# MINI_SAM_D51_r017_b002_A.net
KiCad netlist of a schematic drawn in EAGLE
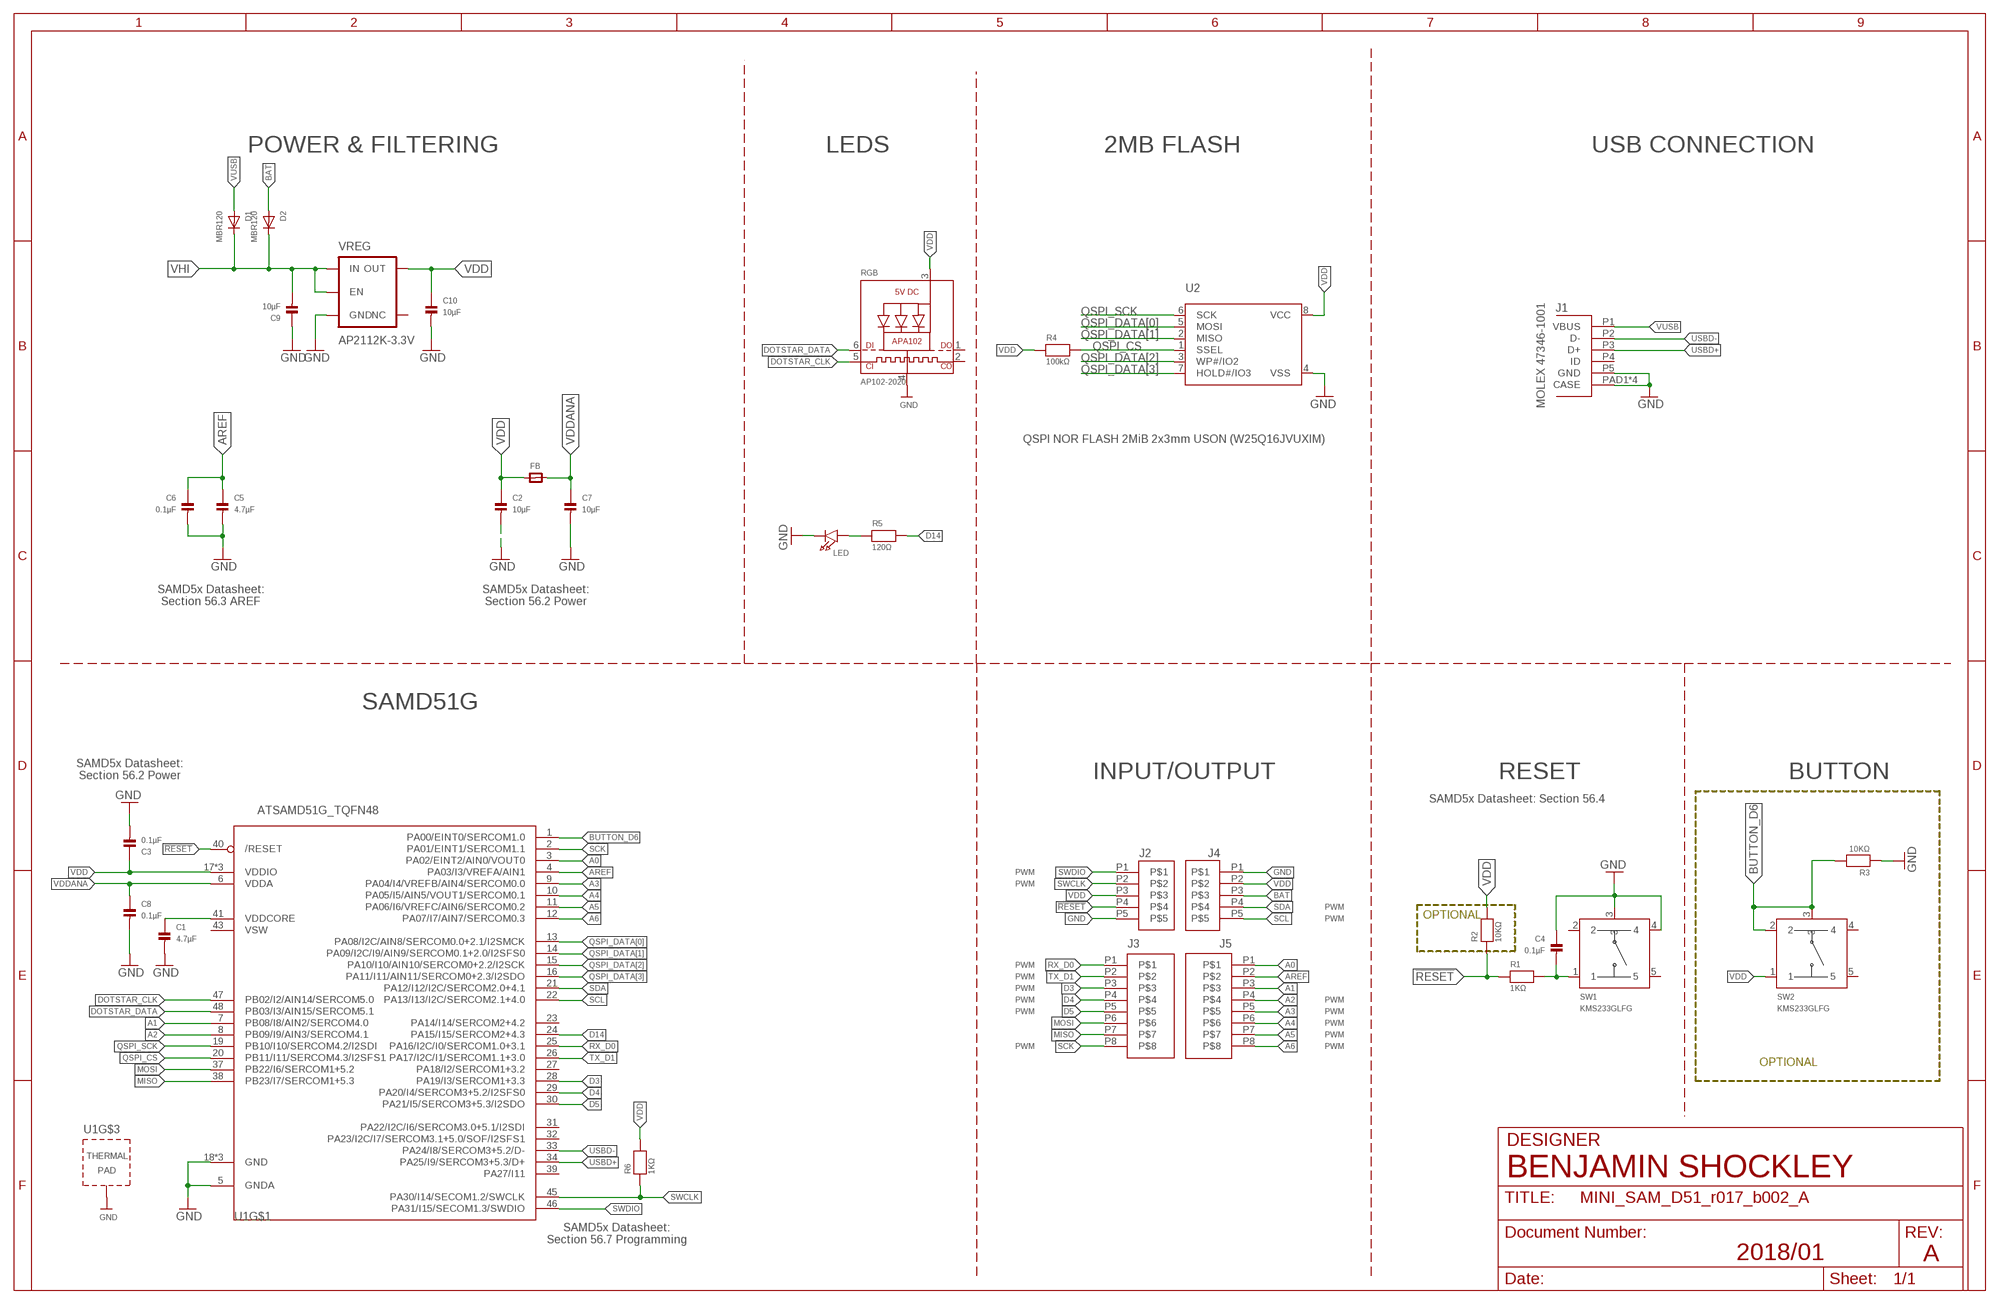
[diagram p0: schematic, sheet 1]

(export (version "E")
  (design (tool "Eeschema 10.0.6"))
  (components
    (comp (ref "C1")
      (value "4.7µF")
      (footprint "eagle-import:_0603MP")
      (libsource (lib "eagle-import") (part "CAP_CERAMIC_0603MP"))
    )
    (comp (ref "C2")
      (value "10µF")
      (footprint "eagle-import:_0603MP")
      (libsource (lib "eagle-import") (part "CAP_CERAMIC_0603MP"))
    )
    (comp (ref "C3")
      (value "0.1µF")
      (footprint "eagle-import:_0603MP")
      (libsource (lib "eagle-import") (part "CAP_CERAMIC_0603MP"))
    )
    (comp (ref "C4")
      (value "0.1µF")
      (footprint "eagle-import:_0603MP")
      (libsource (lib "eagle-import") (part "CAP_CERAMIC_0603MP"))
    )
    (comp (ref "C5")
      (value "4.7µF")
      (footprint "eagle-import:_0603MP")
      (libsource (lib "eagle-import") (part "CAP_CERAMIC_0603MP"))
    )
    (comp (ref "C6")
      (value "0.1µF")
      (footprint "eagle-import:_0603MP")
      (libsource (lib "eagle-import") (part "CAP_CERAMIC_0603MP"))
    )
    (comp (ref "C7")
      (value "10µF")
      (footprint "eagle-import:_0603MP")
      (libsource (lib "eagle-import") (part "CAP_CERAMIC_0603MP"))
    )
    (comp (ref "C8")
      (value "0.1µF")
      (footprint "eagle-import:_0603MP")
      (libsource (lib "eagle-import") (part "CAP_CERAMIC_0603MP"))
    )
    (comp (ref "C9")
      (value "10µF")
      (footprint "eagle-import:_0603MP")
      (libsource (lib "eagle-import") (part "CAP_CERAMIC_0603MP"))
    )
    (comp (ref "C10")
      (value "10µF")
      (footprint "eagle-import:_0603MP")
      (libsource (lib "eagle-import") (part "CAP_CERAMIC_0603MP"))
    )
    (comp (ref "D1")
      (value "MBR120")
      (footprint "eagle-import:SOD-123FL")
      (libsource (lib "eagle-import") (part "DIODE_SOD-123FL"))
    )
    (comp (ref "D2")
      (value "MBR120")
      (footprint "eagle-import:SOD-123FL")
      (libsource (lib "eagle-import") (part "DIODE_SOD-123FL"))
    )
    (comp (ref "FB")
      (value "Impedence: 50 ohm @ 20 MHz, 220 Ohm @ 100 MHz; low DC resistance")
      (footprint "eagle-import:_0603MP")
      (libsource (lib "eagle-import") (part "FERRITE_0603MP"))
    )
    (comp (ref "J1")
      (value "MOLEX_47346-100147346")
      (footprint "eagle-import:MOLEX_47346-1001")
      (libsource (lib "eagle-import") (part "MOLEX_47346-100147346"))
    )
    (comp (ref "J2")
      (value "1X5_HEADER_1.27MMCAST")
      (footprint "eagle-import:1X5_HEADER_1.27MM_CASTELLATED")
      (libsource (lib "eagle-import") (part "1X5_HEADER_1.27MMCAST"))
    )
    (comp (ref "J3")
      (value "1X8_HEADER_1.27MMCAST")
      (footprint "eagle-import:1X8_HEADER_1.27MM_CASTELLATED")
      (libsource (lib "eagle-import") (part "1X8_HEADER_1.27MMCAST"))
    )
    (comp (ref "J4")
      (value "1X5_HEADER_1.27MMCAST")
      (footprint "eagle-import:1X5_HEADER_1.27MM_CASTELLATED")
      (libsource (lib "eagle-import") (part "1X5_HEADER_1.27MMCAST"))
    )
    (comp (ref "J5")
      (value "1X8_HEADER_1.27MMCAST")
      (footprint "eagle-import:1X8_HEADER_1.27MM_CASTELLATED")
      (libsource (lib "eagle-import") (part "1X8_HEADER_1.27MMCAST"))
    )
    (comp (ref "LED")
      (value "VLRK31Q1R2-GS08")
      (footprint "eagle-import:REVERSE_MOUNT_LED")
      (libsource (lib "eagle-import") (part "REVERSEMOUNTLED"))
    )
    (comp (ref "R1")
      (value "1KΩ")
      (footprint "eagle-import:_0603MP")
      (libsource (lib "eagle-import") (part "RESISTOR_0603MP"))
    )
    (comp (ref "R2")
      (value "10KΩ")
      (footprint "eagle-import:_0603MP")
      (libsource (lib "eagle-import") (part "RESISTOR_0603MP"))
    )
    (comp (ref "R3")
      (value "10KΩ")
      (footprint "eagle-import:_0603MP")
      (libsource (lib "eagle-import") (part "RESISTOR_0603MP"))
    )
    (comp (ref "R4")
      (value "100kΩ")
      (footprint "eagle-import:_0603MP")
      (libsource (lib "eagle-import") (part "RESISTOR_0603MP"))
    )
    (comp (ref "R5")
      (value "120Ω")
      (footprint "eagle-import:_0603MP")
      (libsource (lib "eagle-import") (part "RESISTOR_0603MP"))
    )
    (comp (ref "R6")
      (value "1KΩ")
      (footprint "eagle-import:_0603MP")
      (libsource (lib "eagle-import") (part "RESISTOR_0603MP"))
    )
    (comp (ref "RGB")
      (value "AP102-2020")
      (footprint "eagle-import:APA102_2020")
      (libsource (lib "eagle-import") (part "APA1022020"))
    )
    (comp (ref "SW1")
      (value "KMS233GLFG")
      (footprint "eagle-import:KMS_SWITCH")
      (libsource (lib "eagle-import") (part "KMS_SWITCHKMS"))
    )
    (comp (ref "SW2")
      (value "KMS233GLFG")
      (footprint "eagle-import:KMS_SWITCH")
      (libsource (lib "eagle-import") (part "KMS_SWITCHKMS"))
    )
    (comp (ref "U1")
      (value "ATSAMD51G_TQFN48")
      (footprint "eagle-import:TQFN48_7MM")
      (libsource (lib "eagle-import") (part "ATSAMD51G_TQFN48"))
    )
    (comp (ref "U2")
      (value "QSPI NOR FLASH 2MiB 2x3mm USON (W25Q16JVUXIM)")
      (footprint "eagle-import:USON8")
      (libsource (lib "eagle-import") (part "SPIFLASH_8PINUX"))
    )
    (comp (ref "VREG")
      (value "AP2112K-3.3V")
      (footprint "eagle-import:SOT23-5")
      (libsource (lib "eagle-import") (part "V_REG_AP2112K-3.3V"))
    )
  )
  (nets
    (net (code "1") (name "/VSW") (class "Default")
      (node (ref "U1") (pin "43") (pinfunction "VSW_43") (pintype "power_in"))
    )
    (net (code "2") (name "/~{RESET}") (class "Default")
      (node (ref "J2") (pin "P4") (pinfunction "P$4_P4") (pintype "bidirectional"))
      (node (ref "R1") (pin "1") (pinfunction "1_1") (pintype "passive"))
      (node (ref "R2") (pin "1") (pinfunction "1_1") (pintype "passive"))
      (node (ref "U1") (pin "40") (pinfunction "/RESET_40") (pintype "bidirectional"))
    )
    (net (code "3") (name "A0") (class "Default")
      (node (ref "J5") (pin "P1") (pinfunction "P$1_P1") (pintype "bidirectional"))
      (node (ref "U1") (pin "3") (pinfunction "PA02/EINT2/AIN0/VOUT0_3") (pintype "bidirectional"))
    )
    (net (code "4") (name "A1") (class "Default")
      (node (ref "J5") (pin "P3") (pinfunction "P$3_P3") (pintype "bidirectional"))
      (node (ref "U1") (pin "7") (pinfunction "PB08/I8/AIN2/SERCOM4.0_7") (pintype "bidirectional"))
    )
    (net (code "5") (name "A2") (class "Default")
      (node (ref "J5") (pin "P4") (pinfunction "P$4_P4") (pintype "bidirectional"))
      (node (ref "U1") (pin "8") (pinfunction "PB09/I9/AIN3/SERCOM4.1_8") (pintype "bidirectional"))
    )
    (net (code "6") (name "A3") (class "Default")
      (node (ref "J5") (pin "P5") (pinfunction "P$5_P5") (pintype "bidirectional"))
      (node (ref "U1") (pin "9") (pinfunction "PA04/I4/VREFB/AIN4/SERCOM0.0_9") (pintype "bidirectional"))
    )
    (net (code "7") (name "A4") (class "Default")
      (node (ref "J5") (pin "P6") (pinfunction "P$6_P6") (pintype "bidirectional"))
      (node (ref "U1") (pin "10") (pinfunction "PA05/I5/AIN5/VOUT1/SERCOM0.1_10") (pintype "bidirectional"))
    )
    (net (code "8") (name "A5") (class "Default")
      (node (ref "J5") (pin "P7") (pinfunction "P$7_P7") (pintype "bidirectional"))
      (node (ref "U1") (pin "11") (pinfunction "PA06/I6/VREFC/AIN6/SERCOM0.2_11") (pintype "bidirectional"))
    )
    (net (code "9") (name "A6") (class "Default")
      (node (ref "J5") (pin "P8") (pinfunction "P$8_P8") (pintype "bidirectional"))
      (node (ref "U1") (pin "12") (pinfunction "PA07/I7/AIN7/SERCOM0.3_12") (pintype "bidirectional"))
    )
    (net (code "10") (name "AREF") (class "Default")
      (node (ref "C5") (pin "1") (pinfunction "P$1_1") (pintype "passive"))
      (node (ref "C6") (pin "1") (pinfunction "P$1_1") (pintype "passive"))
      (node (ref "J5") (pin "P2") (pinfunction "P$2_P2") (pintype "bidirectional"))
      (node (ref "U1") (pin "4") (pinfunction "PA03/I3/VREFA/AIN1_4") (pintype "bidirectional"))
    )
    (net (code "11") (name "BAT") (class "Default")
      (node (ref "D2") (pin "A") (pinfunction "A_A") (pintype "passive"))
      (node (ref "J4") (pin "P3") (pinfunction "P$3_P3") (pintype "bidirectional"))
    )
    (net (code "12") (name "BUTTON_D6") (class "Default")
      (node (ref "R3") (pin "2") (pinfunction "2_2") (pintype "passive"))
      (node (ref "SW2") (pin "2") (pinfunction "2_2") (pintype "bidirectional"))
      (node (ref "SW2") (pin "3") (pinfunction "3_3") (pintype "bidirectional"))
      (node (ref "U1") (pin "1") (pinfunction "PA00/EINT0/SERCOM1.0_1") (pintype "bidirectional"))
    )
    (net (code "13") (name "D3") (class "Default")
      (node (ref "J3") (pin "P3") (pinfunction "P$3_P3") (pintype "bidirectional"))
      (node (ref "U1") (pin "28") (pinfunction "PA19/I3/SERCOM1+3.3_28") (pintype "bidirectional"))
    )
    (net (code "14") (name "D4") (class "Default")
      (node (ref "J3") (pin "P4") (pinfunction "P$4_P4") (pintype "bidirectional"))
      (node (ref "U1") (pin "29") (pinfunction "PA20/I4/SERCOM3+5.2/I2SFS0_29") (pintype "bidirectional"))
    )
    (net (code "15") (name "D5") (class "Default")
      (node (ref "J3") (pin "P5") (pinfunction "P$5_P5") (pintype "bidirectional"))
      (node (ref "U1") (pin "30") (pinfunction "PA21/I5/SERCOM3+5.3/I2SDO_30") (pintype "bidirectional"))
    )
    (net (code "16") (name "D14") (class "Default")
      (node (ref "R5") (pin "2") (pinfunction "2_2") (pintype "passive"))
      (node (ref "U1") (pin "24") (pinfunction "PA15/I15/SERCOM2+4.3_24") (pintype "bidirectional"))
    )
    (net (code "17") (name "DOTSTAR_CLK") (class "Default")
      (node (ref "RGB") (pin "5") (pinfunction "CKI_5") (pintype "input"))
      (node (ref "U1") (pin "47") (pinfunction "PB02/I2/AIN14/SERCOM5.0_47") (pintype "bidirectional"))
    )
    (net (code "18") (name "DOTSTAR_DATA") (class "Default")
      (node (ref "RGB") (pin "6") (pinfunction "DI_6") (pintype "input"))
      (node (ref "U1") (pin "48") (pinfunction "PB03/I3/AIN15/SERCOM5.1_48") (pintype "bidirectional"))
    )
    (net (code "19") (name "GND") (class "Default")
      (node (ref "C1") (pin "2") (pinfunction "P$2_2") (pintype "passive"))
      (node (ref "C10") (pin "2") (pinfunction "P$2_2") (pintype "passive"))
      (node (ref "C2") (pin "2") (pinfunction "P$2_2") (pintype "passive"))
      (node (ref "C3") (pin "2") (pinfunction "P$2_2") (pintype "passive"))
      (node (ref "C4") (pin "1") (pinfunction "P$1_1") (pintype "passive"))
      (node (ref "C5") (pin "2") (pinfunction "P$2_2") (pintype "passive"))
      (node (ref "C6") (pin "2") (pinfunction "P$2_2") (pintype "passive"))
      (node (ref "C7") (pin "2") (pinfunction "P$2_2") (pintype "passive"))
      (node (ref "C8") (pin "2") (pinfunction "P$2_2") (pintype "passive"))
      (node (ref "C9") (pin "1") (pinfunction "P$1_1") (pintype "passive"))
      (node (ref "J1") (pin "P5") (pinfunction "GND_P5") (pintype "power_in"))
      (node (ref "J1") (pin "PAD1") (pinfunction "CASE_PAD1") (pintype "bidirectional"))
      (node (ref "J1") (pin "PAD2") (pinfunction "CASE_PAD2") (pintype "bidirectional"))
      (node (ref "J1") (pin "PAD3") (pinfunction "CASE_PAD3") (pintype "bidirectional"))
      (node (ref "J1") (pin "PAD4") (pinfunction "CASE_PAD4") (pintype "bidirectional"))
      (node (ref "J2") (pin "P5") (pinfunction "P$5_P5") (pintype "bidirectional"))
      (node (ref "J4") (pin "P1") (pinfunction "P$1_P1") (pintype "bidirectional"))
      (node (ref "LED") (pin "C") (pinfunction "C_C") (pintype "passive"))
      (node (ref "R3") (pin "1") (pinfunction "1_1") (pintype "passive"))
      (node (ref "RGB") (pin "4") (pinfunction "GND_4") (pintype "power_in"))
      (node (ref "SW1") (pin "3") (pinfunction "3_3") (pintype "bidirectional"))
      (node (ref "SW1") (pin "4") (pinfunction "4_4") (pintype "bidirectional"))
      (node (ref "U1") (pin "18") (pinfunction "GND_18") (pintype "power_in"))
      (node (ref "U1") (pin "35") (pinfunction "GND_35") (pintype "power_in"))
      (node (ref "U1") (pin "42") (pinfunction "GND_42") (pintype "power_in"))
      (node (ref "U1") (pin "5") (pinfunction "GNDA_5") (pintype "power_in"))
      (node (ref "U1") (pin "THERMAL") (pinfunction "TP_THERMAL") (pintype "power_in"))
      (node (ref "U2") (pin "4") (pinfunction "VSS_4") (pintype "bidirectional"))
      (node (ref "VREG") (pin "2") (pinfunction "GND_2") (pintype "input"))
    )
    (net (code "20") (name "MISO") (class "Default")
      (node (ref "J3") (pin "P7") (pinfunction "P$7_P7") (pintype "bidirectional"))
      (node (ref "U1") (pin "38") (pinfunction "PB23/I7/SERCOM1+5.3_38") (pintype "bidirectional"))
    )
    (net (code "21") (name "MOSI") (class "Default")
      (node (ref "J3") (pin "P6") (pinfunction "P$6_P6") (pintype "bidirectional"))
      (node (ref "U1") (pin "37") (pinfunction "PB22/I6/SERCOM1+5.2_37") (pintype "bidirectional"))
    )
    (net (code "22") (name "Net-(C1-P$1)") (class "Default")
      (node (ref "C1") (pin "1") (pinfunction "P$1_1") (pintype "passive"))
      (node (ref "U1") (pin "41") (pinfunction "VDDCORE_41") (pintype "power_in"))
    )
    (net (code "23") (name "Net-(C4-P$2)") (class "Default")
      (node (ref "C4") (pin "2") (pinfunction "P$2_2") (pintype "passive"))
      (node (ref "R1") (pin "2") (pinfunction "2_2") (pintype "passive"))
      (node (ref "SW1") (pin "1") (pinfunction "1_1") (pintype "bidirectional"))
    )
    (net (code "24") (name "Net-(LED-PadA)") (class "Default")
      (node (ref "LED") (pin "A") (pinfunction "A_A") (pintype "passive"))
      (node (ref "R5") (pin "1") (pinfunction "1_1") (pintype "passive"))
    )
    (net (code "25") (name "QSPI_CS") (class "Default")
      (node (ref "R4") (pin "2") (pinfunction "2_2") (pintype "passive"))
      (node (ref "U1") (pin "20") (pinfunction "PB11/I11/SERCOM4.3/I2SFS1_20") (pintype "bidirectional"))
      (node (ref "U2") (pin "1") (pinfunction "SSEL_1") (pintype "bidirectional"))
    )
    (net (code "26") (name "QSPI_DATA[0]") (class "Default")
      (node (ref "U1") (pin "13") (pinfunction "PA08/I2C/AIN8/SERCOM0.0+2.1/I2SMCK_13") (pintype "bidirectional"))
      (node (ref "U2") (pin "5") (pinfunction "MOSI_5") (pintype "bidirectional"))
    )
    (net (code "27") (name "QSPI_DATA[1]") (class "Default")
      (node (ref "U1") (pin "14") (pinfunction "PA09/I2C/I9/AIN9/SERCOM0.1+2.0/I2SFS0_14") (pintype "bidirectional"))
      (node (ref "U2") (pin "2") (pinfunction "MISO_2") (pintype "bidirectional"))
    )
    (net (code "28") (name "QSPI_DATA[2]") (class "Default")
      (node (ref "U1") (pin "15") (pinfunction "PA10/I10/AIN10/SERCOM0+2.2/I2SCK_15") (pintype "bidirectional"))
      (node (ref "U2") (pin "3") (pinfunction "WP#/IO2_3") (pintype "bidirectional"))
    )
    (net (code "29") (name "QSPI_DATA[3]") (class "Default")
      (node (ref "U1") (pin "16") (pinfunction "PA11/I11/AIN11/SERCOM0+2.3/I2SDO_16") (pintype "bidirectional"))
      (node (ref "U2") (pin "7") (pinfunction "HOLD#/IO3_7") (pintype "bidirectional"))
    )
    (net (code "30") (name "QSPI_SCK") (class "Default")
      (node (ref "U1") (pin "19") (pinfunction "PB10/I10/SERCOM4.2/I2SDI_19") (pintype "bidirectional"))
      (node (ref "U2") (pin "6") (pinfunction "SCK_6") (pintype "bidirectional"))
    )
    (net (code "31") (name "RX_D0") (class "Default")
      (node (ref "J3") (pin "P1") (pinfunction "P$1_P1") (pintype "bidirectional"))
      (node (ref "U1") (pin "25") (pinfunction "PA16/I2C/I0/SERCOM1.0+3.1_25") (pintype "bidirectional"))
    )
    (net (code "32") (name "SCK") (class "Default")
      (node (ref "J3") (pin "P8") (pinfunction "P$8_P8") (pintype "bidirectional"))
      (node (ref "U1") (pin "2") (pinfunction "PA01/EINT1/SERCOM1.1_2") (pintype "bidirectional"))
    )
    (net (code "33") (name "SCL") (class "Default")
      (node (ref "J4") (pin "P5") (pinfunction "P$5_P5") (pintype "bidirectional"))
      (node (ref "U1") (pin "22") (pinfunction "PA13/I13/I2C/SERCOM2.1+4.0_22") (pintype "bidirectional"))
    )
    (net (code "34") (name "SDA") (class "Default")
      (node (ref "J4") (pin "P4") (pinfunction "P$4_P4") (pintype "bidirectional"))
      (node (ref "U1") (pin "21") (pinfunction "PA12/I12/I2C/SERCOM2.0+4.1_21") (pintype "bidirectional"))
    )
    (net (code "35") (name "SWCLK") (class "Default")
      (node (ref "J2") (pin "P2") (pinfunction "P$2_P2") (pintype "bidirectional"))
      (node (ref "R6") (pin "1") (pinfunction "1_1") (pintype "passive"))
      (node (ref "U1") (pin "45") (pinfunction "PA30/I14/SECOM1.2/SWCLK_45") (pintype "bidirectional"))
    )
    (net (code "36") (name "SWDIO") (class "Default")
      (node (ref "J2") (pin "P1") (pinfunction "P$1_P1") (pintype "bidirectional"))
      (node (ref "U1") (pin "46") (pinfunction "PA31/I15/SECOM1.3/SWDIO_46") (pintype "bidirectional"))
    )
    (net (code "37") (name "TX_D1") (class "Default")
      (node (ref "J3") (pin "P2") (pinfunction "P$2_P2") (pintype "bidirectional"))
      (node (ref "U1") (pin "26") (pinfunction "PA17/I2C/I1/SERCOM1.1+3.0_26") (pintype "bidirectional"))
    )
    (net (code "38") (name "USBD+") (class "Default")
      (node (ref "J1") (pin "P3") (pinfunction "D+_P3") (pintype "bidirectional"))
      (node (ref "U1") (pin "34") (pinfunction "PA25/I9/SERCOM3+5.3/D+_34") (pintype "bidirectional"))
    )
    (net (code "39") (name "USBD-") (class "Default")
      (node (ref "J1") (pin "P2") (pinfunction "D-_P2") (pintype "bidirectional"))
      (node (ref "U1") (pin "33") (pinfunction "PA24/I8/SERCOM3+5.2/D-_33") (pintype "bidirectional"))
    )
    (net (code "40") (name "VDD") (class "Default")
      (node (ref "C10") (pin "1") (pinfunction "P$1_1") (pintype "passive"))
      (node (ref "C2") (pin "1") (pinfunction "P$1_1") (pintype "passive"))
      (node (ref "C3") (pin "1") (pinfunction "P$1_1") (pintype "passive"))
      (node (ref "FB") (pin "1") (pinfunction "P$1_1") (pintype "passive"))
      (node (ref "J2") (pin "P3") (pinfunction "P$3_P3") (pintype "bidirectional"))
      (node (ref "J4") (pin "P2") (pinfunction "P$2_P2") (pintype "bidirectional"))
      (node (ref "R2") (pin "2") (pinfunction "2_2") (pintype "passive"))
      (node (ref "R4") (pin "1") (pinfunction "1_1") (pintype "passive"))
      (node (ref "R6") (pin "2") (pinfunction "2_2") (pintype "passive"))
      (node (ref "RGB") (pin "3") (pinfunction "VDD_3") (pintype "power_in"))
      (node (ref "SW2") (pin "1") (pinfunction "1_1") (pintype "bidirectional"))
      (node (ref "U1") (pin "17") (pinfunction "VDDIO_17") (pintype "power_in"))
      (node (ref "U1") (pin "36") (pinfunction "VDDIO_36") (pintype "power_in"))
      (node (ref "U1") (pin "44") (pinfunction "VDDIO_44") (pintype "power_in"))
      (node (ref "U2") (pin "8") (pinfunction "VCC_8") (pintype "bidirectional"))
      (node (ref "VREG") (pin "5") (pinfunction "OUT_5") (pintype "passive"))
    )
    (net (code "41") (name "VDDANA") (class "Default")
      (node (ref "C7") (pin "1") (pinfunction "P$1_1") (pintype "passive"))
      (node (ref "C8") (pin "1") (pinfunction "P$1_1") (pintype "passive"))
      (node (ref "FB") (pin "2") (pinfunction "P$2_2") (pintype "passive"))
      (node (ref "U1") (pin "6") (pinfunction "VDDA_6") (pintype "power_in"))
    )
    (net (code "42") (name "VHI") (class "Default")
      (node (ref "C9") (pin "2") (pinfunction "P$2_2") (pintype "passive"))
      (node (ref "D1") (pin "C") (pinfunction "C_C") (pintype "passive"))
      (node (ref "D2") (pin "C") (pinfunction "C_C") (pintype "passive"))
      (node (ref "VREG") (pin "1") (pinfunction "IN_1") (pintype "input"))
      (node (ref "VREG") (pin "3") (pinfunction "EN_3") (pintype "input"))
    )
    (net (code "43") (name "VUSB") (class "Default")
      (node (ref "D1") (pin "A") (pinfunction "A_A") (pintype "passive"))
      (node (ref "J1") (pin "P1") (pinfunction "VBUS_P1") (pintype "power_in"))
    )
    (net (code "44") (name "unconnected-(J1-ID-PadP4)") (class "Default")
      (node (ref "J1") (pin "P4") (pinfunction "ID_P4") (pintype "bidirectional"))
    )
    (net (code "45") (name "unconnected-(RGB-CKO-Pad2)") (class "Default")
      (node (ref "RGB") (pin "2") (pinfunction "CKO_2") (pintype "output"))
    )
    (net (code "46") (name "unconnected-(RGB-DO-Pad1)") (class "Default")
      (node (ref "RGB") (pin "1") (pinfunction "DO_1") (pintype "output"))
    )
    (net (code "47") (name "unconnected-(SW1-Pad2)") (class "Default")
      (node (ref "SW1") (pin "2") (pinfunction "2_2") (pintype "bidirectional"))
    )
    (net (code "48") (name "unconnected-(SW1-Pad5)") (class "Default")
      (node (ref "SW1") (pin "5") (pinfunction "5_5") (pintype "bidirectional"))
    )
    (net (code "49") (name "unconnected-(SW2-Pad4)") (class "Default")
      (node (ref "SW2") (pin "4") (pinfunction "4_4") (pintype "bidirectional"))
    )
    (net (code "50") (name "unconnected-(SW2-Pad5)") (class "Default")
      (node (ref "SW2") (pin "5") (pinfunction "5_5") (pintype "bidirectional"))
    )
    (net (code "51") (name "unconnected-(U1A-PA14{slash}I14{slash}SERCOM2+4.2-Pad23)") (class "Default")
      (node (ref "U1") (pin "23") (pinfunction "PA14/I14/SERCOM2+4.2_23") (pintype "bidirectional"))
    )
    (net (code "52") (name "unconnected-(U1A-PA18{slash}I2{slash}SERCOM1+3.2-Pad27)") (class "Default")
      (node (ref "U1") (pin "27") (pinfunction "PA18/I2/SERCOM1+3.2_27") (pintype "bidirectional"))
    )
    (net (code "53") (name "unconnected-(U1A-PA22{slash}I2C{slash}I6{slash}SERCOM3.0+5.1{slash}I2SDI-Pad31)") (class "Default")
      (node (ref "U1") (pin "31") (pinfunction "PA22/I2C/I6/SERCOM3.0+5.1/I2SDI_31") (pintype "bidirectional"))
    )
    (net (code "54") (name "unconnected-(U1A-PA23{slash}I2C{slash}I7{slash}SERCOM3.1+5.0{slash}SOF{slash}I2SFS1-Pad32)") (class "Default")
      (node (ref "U1") (pin "32") (pinfunction "PA23/I2C/I7/SERCOM3.1+5.0/SOF/I2SFS1_32") (pintype "bidirectional"))
    )
    (net (code "55") (name "unconnected-(U1A-PA27{slash}I11-Pad39)") (class "Default")
      (node (ref "U1") (pin "39") (pinfunction "PA27/I11_39") (pintype "bidirectional"))
    )
    (net (code "56") (name "unconnected-(VREG-NC-Pad4)") (class "Default")
      (node (ref "VREG") (pin "4") (pinfunction "NC_4") (pintype "input"))
    )
  )
)
